# GBASP_USB-C.net
KiCad netlist of a schematic drawn in EAGLE
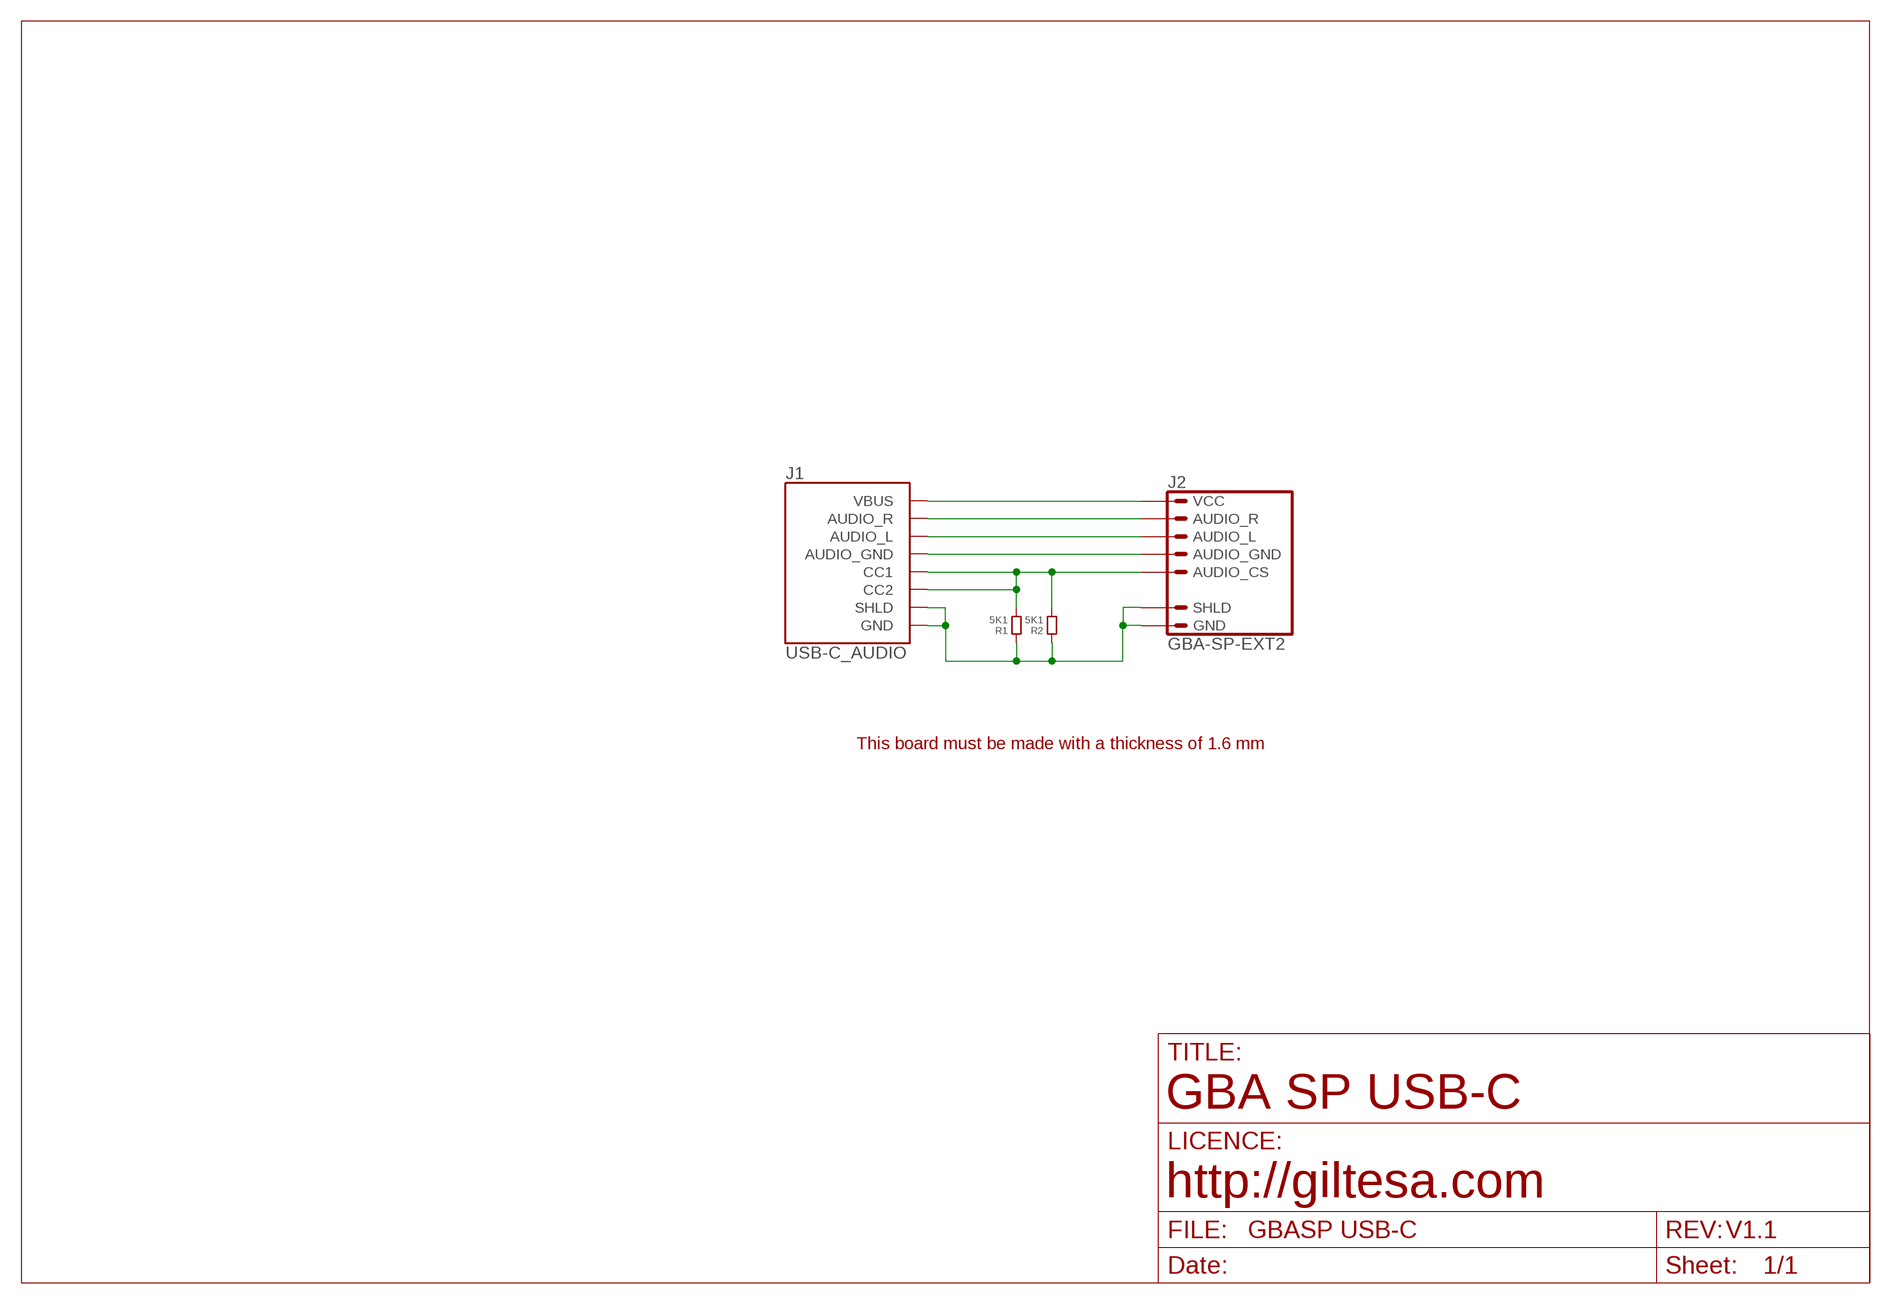
[diagram p0: schematic, sheet 1]

(export (version "E")
  (design (tool "Eeschema 10.0.6"))
  (components
    (comp (ref "J1")
      (value "USB-C_AUDIO")
      (footprint "eagle-import:USB-C_16P_3SHLD")
      (libsource (lib "eagle-import") (part "USB-C_POWER_AUDIOGBASP"))
    )
    (comp (ref "J2")
      (value "GBA-SP-EXT2")
      (footprint "eagle-import:GBA-SP-EXT2")
      (libsource (lib "eagle-import") (part "GBA-SP-EXT2"))
    )
    (comp (ref "R1")
      (value "5K1")
      (footprint "eagle-import:0402")
      (libsource (lib "eagle-import") (part "RESISTOR.0402"))
    )
    (comp (ref "R2")
      (value "5K1")
      (footprint "eagle-import:0402")
      (libsource (lib "eagle-import") (part "RESISTOR.0402"))
    )
  )
  (nets
    (net (code "1") (name "Net-(J1-AUDIO_GND-PadA8)") (class "Default")
      (node (ref "J1") (pin "A8") (pinfunction "AUDIO_GND_A8") (pintype "bidirectional"))
      (node (ref "J1") (pin "B8") (pinfunction "AUDIO_GND_B8") (pintype "bidirectional"))
      (node (ref "J2") (pin "AUDIO_GND") (pinfunction "AUDIO_GND_AUDIO_GND") (pintype "passive"))
    )
    (net (code "2") (name "Net-(J1-AUDIO_L-PadA7)") (class "Default")
      (node (ref "J1") (pin "A7") (pinfunction "AUDIO_L_A7") (pintype "bidirectional"))
      (node (ref "J1") (pin "B7") (pinfunction "AUDIO_L_B7") (pintype "bidirectional"))
      (node (ref "J2") (pin "AUDIO_L") (pinfunction "AUDIO_L_AUDIO_L") (pintype "passive"))
    )
    (net (code "3") (name "Net-(J1-AUDIO_R-PadA6)") (class "Default")
      (node (ref "J1") (pin "A6") (pinfunction "AUDIO_R_A6") (pintype "bidirectional"))
      (node (ref "J1") (pin "B6") (pinfunction "AUDIO_R_B6") (pintype "bidirectional"))
      (node (ref "J2") (pin "AUDIO_R") (pinfunction "AUDIO_R_AUDIO_R") (pintype "passive"))
    )
    (net (code "4") (name "Net-(J1-CC1)") (class "Default")
      (node (ref "J1") (pin "A5") (pinfunction "CC1_A5") (pintype "bidirectional"))
      (node (ref "J1") (pin "B5") (pinfunction "CC2_B5") (pintype "bidirectional"))
      (node (ref "J2") (pin "AUDIO_CS") (pinfunction "AUDIO_CS_AUDIO_CS") (pintype "passive"))
      (node (ref "R1") (pin "2") (pinfunction "2_2") (pintype "bidirectional"))
      (node (ref "R2") (pin "2") (pinfunction "2_2") (pintype "bidirectional"))
    )
    (net (code "5") (name "Net-(J1-GND-PadGND2)") (class "Default")
      (node (ref "J1") (pin "GND") (pinfunction "GND_GND") (pintype "bidirectional"))
      (node (ref "J1") (pin "GND2") (pinfunction "GND_GND2") (pintype "bidirectional"))
      (node (ref "J1") (pin "SHLD1") (pinfunction "SHLD_SHLD1") (pintype "bidirectional"))
      (node (ref "J1") (pin "SHLD3") (pinfunction "SHLD_SHLD3") (pintype "bidirectional"))
      (node (ref "J1") (pin "SHLD4") (pinfunction "SHLD_SHLD4") (pintype "bidirectional"))
      (node (ref "J1") (pin "SHLD5") (pinfunction "SHLD_SHLD5") (pintype "bidirectional"))
      (node (ref "J1") (pin "SHLD6") (pinfunction "SHLD_SHLD6") (pintype "bidirectional"))
      (node (ref "J1") (pin "SHLD7") (pinfunction "SHLD_SHLD7") (pintype "bidirectional"))
      (node (ref "J1") (pin "SHLD8") (pinfunction "SHLD_SHLD8") (pintype "bidirectional"))
      (node (ref "J2") (pin "GND") (pinfunction "GND_GND") (pintype "passive"))
      (node (ref "J2") (pin "SHLD1") (pinfunction "SHLD_SHLD1") (pintype "passive"))
      (node (ref "J2") (pin "SHLD2") (pinfunction "SHLD_SHLD2") (pintype "passive"))
      (node (ref "J2") (pin "SHLD3") (pinfunction "SHLD_SHLD3") (pintype "passive"))
      (node (ref "J2") (pin "SHLD4") (pinfunction "SHLD_SHLD4") (pintype "passive"))
      (node (ref "R1") (pin "1") (pinfunction "1_1") (pintype "bidirectional"))
      (node (ref "R2") (pin "1") (pinfunction "1_1") (pintype "bidirectional"))
    )
    (net (code "6") (name "Net-(J1-VBUS-PadVBUS1)") (class "Default")
      (node (ref "J1") (pin "VBUS1") (pinfunction "VBUS_VBUS1") (pintype "bidirectional"))
      (node (ref "J1") (pin "VBUS2") (pinfunction "VBUS_VBUS2") (pintype "bidirectional"))
      (node (ref "J2") (pin "VCC") (pinfunction "VCC_VCC") (pintype "passive"))
    )
  )
)
